# Interface_Pinboard.net
KiCad netlist of a schematic drawn in Altium Designer
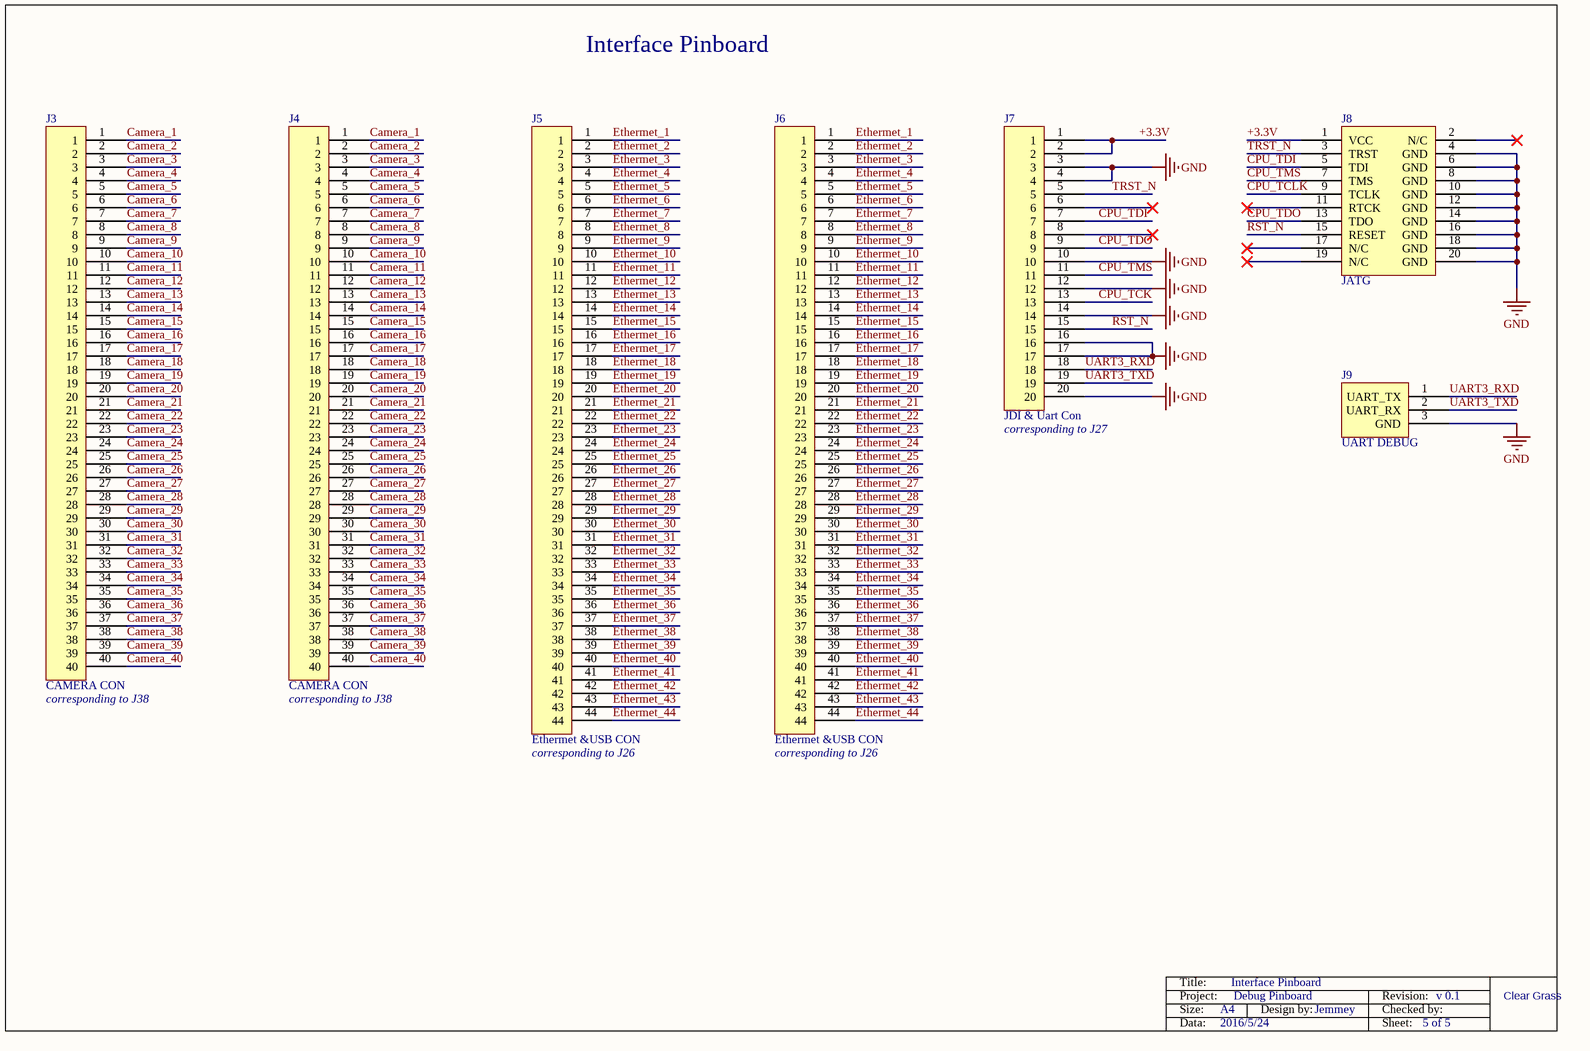
[diagram p0: Interface Pinboard.SchDoc]

(export (version "E")
  (design (tool "Eeschema 10.0.6"))
  (components
    (comp (ref "J3") (value "CAMERA CON") (libsource (lib "Debug Pinborad") (part "CAMERA CON")))
    (comp (ref "J4") (value "CAMERA CON") (libsource (lib "Debug Pinborad") (part "CAMERA CON")))
    (comp (ref "J5")
      (value "Ethermet &USB CON")
      (libsource (lib "Debug Pinborad") (part "Ethermet &USB CON"))
    )
    (comp (ref "J6")
      (value "Ethermet &USB CON")
      (libsource (lib "Debug Pinborad") (part "Ethermet &USB CON"))
    )
    (comp (ref "J7") (value "JDI & Uart Con") (libsource (lib "Debug Pinborad") (part "JDI & Uart Con")))
    (comp (ref "J8") (value "JATG") (libsource (lib "Debug Pinborad") (part "JATG")))
    (comp (ref "J9") (value "UART DEBUG") (libsource (lib "Debug Pinborad") (part "CON")))
  )
  (nets
    (net (code "1") (name "/+3.3V") (class "Default")
      (node (ref "J7") (pin "1") (pinfunction "1_1") (pintype "passive"))
      (node (ref "J7") (pin "2") (pinfunction "2_2") (pintype "passive"))
      (node (ref "J8") (pin "1") (pinfunction "VCC_1") (pintype "passive"))
    )
    (net (code "2") (name "/CPU_TCK") (class "Default")
      (node (ref "J7") (pin "13") (pinfunction "13_13") (pintype "passive"))
    )
    (net (code "3") (name "/CPU_TCLK") (class "Default")
      (node (ref "J8") (pin "9") (pinfunction "TCLK_9") (pintype "passive"))
    )
    (net (code "4") (name "/CPU_TDI") (class "Default")
      (node (ref "J7") (pin "7") (pinfunction "7_7") (pintype "passive"))
      (node (ref "J8") (pin "5") (pinfunction "TDI_5") (pintype "passive"))
    )
    (net (code "5") (name "/CPU_TDO") (class "Default")
      (node (ref "J7") (pin "9") (pinfunction "9_9") (pintype "passive"))
      (node (ref "J8") (pin "13") (pinfunction "TDO_13") (pintype "passive"))
    )
    (net (code "6") (name "/CPU_TMS") (class "Default")
      (node (ref "J7") (pin "11") (pinfunction "11_11") (pintype "passive"))
      (node (ref "J8") (pin "7") (pinfunction "TMS_7") (pintype "passive"))
    )
    (net (code "7") (name "/Camera_1") (class "Default")
      (node (ref "J3") (pin "1") (pinfunction "1_1") (pintype "passive"))
      (node (ref "J4") (pin "1") (pinfunction "1_1") (pintype "passive"))
    )
    (net (code "8") (name "/Camera_2") (class "Default")
      (node (ref "J3") (pin "2") (pinfunction "2_2") (pintype "passive"))
      (node (ref "J4") (pin "2") (pinfunction "2_2") (pintype "passive"))
    )
    (net (code "9") (name "/Camera_3") (class "Default")
      (node (ref "J3") (pin "3") (pinfunction "3_3") (pintype "passive"))
      (node (ref "J4") (pin "3") (pinfunction "3_3") (pintype "passive"))
    )
    (net (code "10") (name "/Camera_4") (class "Default")
      (node (ref "J3") (pin "4") (pinfunction "4_4") (pintype "passive"))
      (node (ref "J4") (pin "4") (pinfunction "4_4") (pintype "passive"))
    )
    (net (code "11") (name "/Camera_5") (class "Default")
      (node (ref "J3") (pin "5") (pinfunction "5_5") (pintype "passive"))
      (node (ref "J4") (pin "5") (pinfunction "5_5") (pintype "passive"))
    )
    (net (code "12") (name "/Camera_6") (class "Default")
      (node (ref "J3") (pin "6") (pinfunction "6_6") (pintype "passive"))
      (node (ref "J4") (pin "6") (pinfunction "6_6") (pintype "passive"))
    )
    (net (code "13") (name "/Camera_7") (class "Default")
      (node (ref "J3") (pin "7") (pinfunction "7_7") (pintype "passive"))
      (node (ref "J4") (pin "7") (pinfunction "7_7") (pintype "passive"))
    )
    (net (code "14") (name "/Camera_8") (class "Default")
      (node (ref "J3") (pin "8") (pinfunction "8_8") (pintype "passive"))
      (node (ref "J4") (pin "8") (pinfunction "8_8") (pintype "passive"))
    )
    (net (code "15") (name "/Camera_9") (class "Default")
      (node (ref "J3") (pin "9") (pinfunction "9_9") (pintype "passive"))
      (node (ref "J4") (pin "9") (pinfunction "9_9") (pintype "passive"))
    )
    (net (code "16") (name "/Camera_10") (class "Default")
      (node (ref "J3") (pin "10") (pinfunction "10_10") (pintype "passive"))
      (node (ref "J4") (pin "10") (pinfunction "10_10") (pintype "passive"))
    )
    (net (code "17") (name "/Camera_11") (class "Default")
      (node (ref "J3") (pin "11") (pinfunction "11_11") (pintype "passive"))
      (node (ref "J4") (pin "11") (pinfunction "11_11") (pintype "passive"))
    )
    (net (code "18") (name "/Camera_12") (class "Default")
      (node (ref "J3") (pin "12") (pinfunction "12_12") (pintype "passive"))
      (node (ref "J4") (pin "12") (pinfunction "12_12") (pintype "passive"))
    )
    (net (code "19") (name "/Camera_13") (class "Default")
      (node (ref "J3") (pin "13") (pinfunction "13_13") (pintype "passive"))
      (node (ref "J4") (pin "13") (pinfunction "13_13") (pintype "passive"))
    )
    (net (code "20") (name "/Camera_14") (class "Default")
      (node (ref "J3") (pin "14") (pinfunction "14_14") (pintype "passive"))
      (node (ref "J4") (pin "14") (pinfunction "14_14") (pintype "passive"))
    )
    (net (code "21") (name "/Camera_15") (class "Default")
      (node (ref "J3") (pin "15") (pinfunction "15_15") (pintype "passive"))
      (node (ref "J4") (pin "15") (pinfunction "15_15") (pintype "passive"))
    )
    (net (code "22") (name "/Camera_16") (class "Default")
      (node (ref "J3") (pin "16") (pinfunction "16_16") (pintype "passive"))
      (node (ref "J4") (pin "16") (pinfunction "16_16") (pintype "passive"))
    )
    (net (code "23") (name "/Camera_17") (class "Default")
      (node (ref "J3") (pin "17") (pinfunction "17_17") (pintype "passive"))
      (node (ref "J4") (pin "17") (pinfunction "17_17") (pintype "passive"))
    )
    (net (code "24") (name "/Camera_18") (class "Default")
      (node (ref "J3") (pin "18") (pinfunction "18_18") (pintype "passive"))
      (node (ref "J4") (pin "18") (pinfunction "18_18") (pintype "passive"))
    )
    (net (code "25") (name "/Camera_19") (class "Default")
      (node (ref "J3") (pin "19") (pinfunction "19_19") (pintype "passive"))
      (node (ref "J4") (pin "19") (pinfunction "19_19") (pintype "passive"))
    )
    (net (code "26") (name "/Camera_20") (class "Default")
      (node (ref "J3") (pin "20") (pinfunction "20_20") (pintype "passive"))
      (node (ref "J4") (pin "20") (pinfunction "20_20") (pintype "passive"))
    )
    (net (code "27") (name "/Camera_21") (class "Default")
      (node (ref "J3") (pin "21") (pinfunction "21_21") (pintype "passive"))
      (node (ref "J4") (pin "21") (pinfunction "21_21") (pintype "passive"))
    )
    (net (code "28") (name "/Camera_22") (class "Default")
      (node (ref "J3") (pin "22") (pinfunction "22_22") (pintype "passive"))
      (node (ref "J4") (pin "22") (pinfunction "22_22") (pintype "passive"))
    )
    (net (code "29") (name "/Camera_23") (class "Default")
      (node (ref "J3") (pin "23") (pinfunction "23_23") (pintype "passive"))
      (node (ref "J4") (pin "23") (pinfunction "23_23") (pintype "passive"))
    )
    (net (code "30") (name "/Camera_24") (class "Default")
      (node (ref "J3") (pin "24") (pinfunction "24_24") (pintype "passive"))
      (node (ref "J4") (pin "24") (pinfunction "24_24") (pintype "passive"))
    )
    (net (code "31") (name "/Camera_25") (class "Default")
      (node (ref "J3") (pin "25") (pinfunction "25_25") (pintype "passive"))
      (node (ref "J4") (pin "25") (pinfunction "25_25") (pintype "passive"))
    )
    (net (code "32") (name "/Camera_26") (class "Default")
      (node (ref "J3") (pin "26") (pinfunction "26_26") (pintype "passive"))
      (node (ref "J4") (pin "26") (pinfunction "26_26") (pintype "passive"))
    )
    (net (code "33") (name "/Camera_27") (class "Default")
      (node (ref "J3") (pin "27") (pinfunction "27_27") (pintype "passive"))
      (node (ref "J4") (pin "27") (pinfunction "27_27") (pintype "passive"))
    )
    (net (code "34") (name "/Camera_28") (class "Default")
      (node (ref "J3") (pin "28") (pinfunction "28_28") (pintype "passive"))
      (node (ref "J4") (pin "28") (pinfunction "28_28") (pintype "passive"))
    )
    (net (code "35") (name "/Camera_29") (class "Default")
      (node (ref "J3") (pin "29") (pinfunction "29_29") (pintype "passive"))
      (node (ref "J4") (pin "29") (pinfunction "29_29") (pintype "passive"))
    )
    (net (code "36") (name "/Camera_30") (class "Default")
      (node (ref "J3") (pin "30") (pinfunction "30_30") (pintype "passive"))
      (node (ref "J4") (pin "30") (pinfunction "30_30") (pintype "passive"))
    )
    (net (code "37") (name "/Camera_31") (class "Default")
      (node (ref "J3") (pin "31") (pinfunction "31_31") (pintype "passive"))
      (node (ref "J4") (pin "31") (pinfunction "31_31") (pintype "passive"))
    )
    (net (code "38") (name "/Camera_32") (class "Default")
      (node (ref "J3") (pin "32") (pinfunction "32_32") (pintype "passive"))
      (node (ref "J4") (pin "32") (pinfunction "32_32") (pintype "passive"))
    )
    (net (code "39") (name "/Camera_33") (class "Default")
      (node (ref "J3") (pin "33") (pinfunction "33_33") (pintype "passive"))
      (node (ref "J4") (pin "33") (pinfunction "33_33") (pintype "passive"))
    )
    (net (code "40") (name "/Camera_34") (class "Default")
      (node (ref "J3") (pin "34") (pinfunction "34_34") (pintype "passive"))
      (node (ref "J4") (pin "34") (pinfunction "34_34") (pintype "passive"))
    )
    (net (code "41") (name "/Camera_35") (class "Default")
      (node (ref "J3") (pin "35") (pinfunction "35_35") (pintype "passive"))
      (node (ref "J4") (pin "35") (pinfunction "35_35") (pintype "passive"))
    )
    (net (code "42") (name "/Camera_36") (class "Default")
      (node (ref "J3") (pin "36") (pinfunction "36_36") (pintype "passive"))
      (node (ref "J4") (pin "36") (pinfunction "36_36") (pintype "passive"))
    )
    (net (code "43") (name "/Camera_37") (class "Default")
      (node (ref "J3") (pin "37") (pinfunction "37_37") (pintype "passive"))
      (node (ref "J4") (pin "37") (pinfunction "37_37") (pintype "passive"))
    )
    (net (code "44") (name "/Camera_38") (class "Default")
      (node (ref "J3") (pin "38") (pinfunction "38_38") (pintype "passive"))
      (node (ref "J4") (pin "38") (pinfunction "38_38") (pintype "passive"))
    )
    (net (code "45") (name "/Camera_39") (class "Default")
      (node (ref "J3") (pin "39") (pinfunction "39_39") (pintype "passive"))
      (node (ref "J4") (pin "39") (pinfunction "39_39") (pintype "passive"))
    )
    (net (code "46") (name "/Camera_40") (class "Default")
      (node (ref "J3") (pin "40") (pinfunction "40_40") (pintype "passive"))
      (node (ref "J4") (pin "40") (pinfunction "40_40") (pintype "passive"))
    )
    (net (code "47") (name "/Ethermet_1") (class "Default")
      (node (ref "J5") (pin "1") (pinfunction "1_1") (pintype "passive"))
      (node (ref "J6") (pin "1") (pinfunction "1_1") (pintype "passive"))
    )
    (net (code "48") (name "/Ethermet_2") (class "Default")
      (node (ref "J5") (pin "2") (pinfunction "2_2") (pintype "passive"))
      (node (ref "J6") (pin "2") (pinfunction "2_2") (pintype "passive"))
    )
    (net (code "49") (name "/Ethermet_2~{2}") (class "Default")
      (node (ref "J5") (pin "22") (pinfunction "22_22") (pintype "passive"))
      (node (ref "J6") (pin "22") (pinfunction "22_22") (pintype "passive"))
    )
    (net (code "50") (name "/Ethermet_3") (class "Default")
      (node (ref "J5") (pin "3") (pinfunction "3_3") (pintype "passive"))
      (node (ref "J6") (pin "3") (pinfunction "3_3") (pintype "passive"))
    )
    (net (code "51") (name "/Ethermet_4") (class "Default")
      (node (ref "J5") (pin "4") (pinfunction "4_4") (pintype "passive"))
      (node (ref "J6") (pin "4") (pinfunction "4_4") (pintype "passive"))
    )
    (net (code "52") (name "/Ethermet_5") (class "Default")
      (node (ref "J5") (pin "5") (pinfunction "5_5") (pintype "passive"))
      (node (ref "J6") (pin "5") (pinfunction "5_5") (pintype "passive"))
    )
    (net (code "53") (name "/Ethermet_6") (class "Default")
      (node (ref "J5") (pin "6") (pinfunction "6_6") (pintype "passive"))
      (node (ref "J6") (pin "6") (pinfunction "6_6") (pintype "passive"))
    )
    (net (code "54") (name "/Ethermet_7") (class "Default")
      (node (ref "J5") (pin "7") (pinfunction "7_7") (pintype "passive"))
      (node (ref "J6") (pin "7") (pinfunction "7_7") (pintype "passive"))
    )
    (net (code "55") (name "/Ethermet_8") (class "Default")
      (node (ref "J5") (pin "8") (pinfunction "8_8") (pintype "passive"))
      (node (ref "J6") (pin "8") (pinfunction "8_8") (pintype "passive"))
    )
    (net (code "56") (name "/Ethermet_9") (class "Default")
      (node (ref "J5") (pin "9") (pinfunction "9_9") (pintype "passive"))
      (node (ref "J6") (pin "9") (pinfunction "9_9") (pintype "passive"))
    )
    (net (code "57") (name "/Ethermet_10") (class "Default")
      (node (ref "J5") (pin "10") (pinfunction "10_10") (pintype "passive"))
      (node (ref "J6") (pin "10") (pinfunction "10_10") (pintype "passive"))
    )
    (net (code "58") (name "/Ethermet_11") (class "Default")
      (node (ref "J5") (pin "11") (pinfunction "11_11") (pintype "passive"))
      (node (ref "J6") (pin "11") (pinfunction "11_11") (pintype "passive"))
    )
    (net (code "59") (name "/Ethermet_12") (class "Default")
      (node (ref "J5") (pin "12") (pinfunction "12_12") (pintype "passive"))
      (node (ref "J6") (pin "12") (pinfunction "12_12") (pintype "passive"))
    )
    (net (code "60") (name "/Ethermet_13") (class "Default")
      (node (ref "J5") (pin "13") (pinfunction "13_13") (pintype "passive"))
      (node (ref "J6") (pin "13") (pinfunction "13_13") (pintype "passive"))
    )
    (net (code "61") (name "/Ethermet_14") (class "Default")
      (node (ref "J5") (pin "14") (pinfunction "14_14") (pintype "passive"))
      (node (ref "J6") (pin "14") (pinfunction "14_14") (pintype "passive"))
    )
    (net (code "62") (name "/Ethermet_15") (class "Default")
      (node (ref "J5") (pin "15") (pinfunction "15_15") (pintype "passive"))
      (node (ref "J6") (pin "15") (pinfunction "15_15") (pintype "passive"))
    )
    (net (code "63") (name "/Ethermet_16") (class "Default")
      (node (ref "J5") (pin "16") (pinfunction "16_16") (pintype "passive"))
      (node (ref "J6") (pin "16") (pinfunction "16_16") (pintype "passive"))
    )
    (net (code "64") (name "/Ethermet_17") (class "Default")
      (node (ref "J5") (pin "17") (pinfunction "17_17") (pintype "passive"))
      (node (ref "J6") (pin "17") (pinfunction "17_17") (pintype "passive"))
    )
    (net (code "65") (name "/Ethermet_18") (class "Default")
      (node (ref "J5") (pin "18") (pinfunction "18_18") (pintype "passive"))
      (node (ref "J6") (pin "18") (pinfunction "18_18") (pintype "passive"))
    )
    (net (code "66") (name "/Ethermet_19") (class "Default")
      (node (ref "J5") (pin "19") (pinfunction "19_19") (pintype "passive"))
      (node (ref "J6") (pin "19") (pinfunction "19_19") (pintype "passive"))
    )
    (net (code "67") (name "/Ethermet_20") (class "Default")
      (node (ref "J5") (pin "20") (pinfunction "20_20") (pintype "passive"))
      (node (ref "J6") (pin "20") (pinfunction "20_20") (pintype "passive"))
    )
    (net (code "68") (name "/Ethermet_21") (class "Default")
      (node (ref "J5") (pin "21") (pinfunction "21_21") (pintype "passive"))
      (node (ref "J6") (pin "21") (pinfunction "21_21") (pintype "passive"))
    )
    (net (code "69") (name "/Ethermet_23") (class "Default")
      (node (ref "J5") (pin "23") (pinfunction "23_23") (pintype "passive"))
      (node (ref "J6") (pin "23") (pinfunction "23_23") (pintype "passive"))
    )
    (net (code "70") (name "/Ethermet_24") (class "Default")
      (node (ref "J5") (pin "24") (pinfunction "24_24") (pintype "passive"))
      (node (ref "J6") (pin "24") (pinfunction "24_24") (pintype "passive"))
    )
    (net (code "71") (name "/Ethermet_25") (class "Default")
      (node (ref "J5") (pin "25") (pinfunction "25_25") (pintype "passive"))
      (node (ref "J6") (pin "25") (pinfunction "25_25") (pintype "passive"))
    )
    (net (code "72") (name "/Ethermet_26") (class "Default")
      (node (ref "J5") (pin "26") (pinfunction "26_26") (pintype "passive"))
      (node (ref "J6") (pin "26") (pinfunction "26_26") (pintype "passive"))
    )
    (net (code "73") (name "/Ethermet_27") (class "Default")
      (node (ref "J5") (pin "27") (pinfunction "27_27") (pintype "passive"))
      (node (ref "J6") (pin "27") (pinfunction "27_27") (pintype "passive"))
    )
    (net (code "74") (name "/Ethermet_28") (class "Default")
      (node (ref "J5") (pin "28") (pinfunction "28_28") (pintype "passive"))
      (node (ref "J6") (pin "28") (pinfunction "28_28") (pintype "passive"))
    )
    (net (code "75") (name "/Ethermet_29") (class "Default")
      (node (ref "J5") (pin "29") (pinfunction "29_29") (pintype "passive"))
      (node (ref "J6") (pin "29") (pinfunction "29_29") (pintype "passive"))
    )
    (net (code "76") (name "/Ethermet_30") (class "Default")
      (node (ref "J5") (pin "30") (pinfunction "30_30") (pintype "passive"))
      (node (ref "J6") (pin "30") (pinfunction "30_30") (pintype "passive"))
    )
    (net (code "77") (name "/Ethermet_31") (class "Default")
      (node (ref "J5") (pin "31") (pinfunction "31_31") (pintype "passive"))
      (node (ref "J6") (pin "31") (pinfunction "31_31") (pintype "passive"))
    )
    (net (code "78") (name "/Ethermet_32") (class "Default")
      (node (ref "J5") (pin "32") (pinfunction "32_32") (pintype "passive"))
      (node (ref "J6") (pin "32") (pinfunction "32_32") (pintype "passive"))
    )
    (net (code "79") (name "/Ethermet_33") (class "Default")
      (node (ref "J5") (pin "33") (pinfunction "33_33") (pintype "passive"))
      (node (ref "J6") (pin "33") (pinfunction "33_33") (pintype "passive"))
    )
    (net (code "80") (name "/Ethermet_34") (class "Default")
      (node (ref "J5") (pin "34") (pinfunction "34_34") (pintype "passive"))
      (node (ref "J6") (pin "34") (pinfunction "34_34") (pintype "passive"))
    )
    (net (code "81") (name "/Ethermet_35") (class "Default")
      (node (ref "J5") (pin "35") (pinfunction "35_35") (pintype "passive"))
      (node (ref "J6") (pin "35") (pinfunction "35_35") (pintype "passive"))
    )
    (net (code "82") (name "/Ethermet_36") (class "Default")
      (node (ref "J5") (pin "36") (pinfunction "36_36") (pintype "passive"))
      (node (ref "J6") (pin "36") (pinfunction "36_36") (pintype "passive"))
    )
    (net (code "83") (name "/Ethermet_37") (class "Default")
      (node (ref "J5") (pin "37") (pinfunction "37_37") (pintype "passive"))
      (node (ref "J6") (pin "37") (pinfunction "37_37") (pintype "passive"))
    )
    (net (code "84") (name "/Ethermet_38") (class "Default")
      (node (ref "J5") (pin "38") (pinfunction "38_38") (pintype "passive"))
      (node (ref "J6") (pin "38") (pinfunction "38_38") (pintype "passive"))
    )
    (net (code "85") (name "/Ethermet_39") (class "Default")
      (node (ref "J5") (pin "39") (pinfunction "39_39") (pintype "passive"))
      (node (ref "J6") (pin "39") (pinfunction "39_39") (pintype "passive"))
    )
    (net (code "86") (name "/Ethermet_40") (class "Default")
      (node (ref "J5") (pin "40") (pinfunction "40_40") (pintype "passive"))
      (node (ref "J6") (pin "40") (pinfunction "40_40") (pintype "passive"))
    )
    (net (code "87") (name "/Ethermet_41") (class "Default")
      (node (ref "J5") (pin "41") (pinfunction "41_41") (pintype "passive"))
      (node (ref "J6") (pin "41") (pinfunction "41_41") (pintype "passive"))
    )
    (net (code "88") (name "/Ethermet_42") (class "Default")
      (node (ref "J5") (pin "42") (pinfunction "42_42") (pintype "passive"))
      (node (ref "J6") (pin "42") (pinfunction "42_42") (pintype "passive"))
    )
    (net (code "89") (name "/Ethermet_43") (class "Default")
      (node (ref "J5") (pin "43") (pinfunction "43_43") (pintype "passive"))
      (node (ref "J6") (pin "43") (pinfunction "43_43") (pintype "passive"))
    )
    (net (code "90") (name "/Ethermet_44") (class "Default")
      (node (ref "J5") (pin "44") (pinfunction "44_44") (pintype "passive"))
      (node (ref "J6") (pin "44") (pinfunction "44_44") (pintype "passive"))
    )
    (net (code "91") (name "/RST_N") (class "Default")
      (node (ref "J7") (pin "15") (pinfunction "15_15") (pintype "passive"))
      (node (ref "J8") (pin "15") (pinfunction "RESET_15") (pintype "passive"))
    )
    (net (code "92") (name "/TRST_N") (class "Default")
      (node (ref "J7") (pin "5") (pinfunction "5_5") (pintype "passive"))
      (node (ref "J8") (pin "3") (pinfunction "TRST_3") (pintype "passive"))
    )
    (net (code "93") (name "/UART3_RXD") (class "Default")
      (node (ref "J7") (pin "18") (pinfunction "18_18") (pintype "passive"))
      (node (ref "J9") (pin "1") (pinfunction "UART_TX_1") (pintype "passive"))
    )
    (net (code "94") (name "/UART3_TXD") (class "Default")
      (node (ref "J7") (pin "19") (pinfunction "19_19") (pintype "passive"))
      (node (ref "J9") (pin "2") (pinfunction "UART_RX_2") (pintype "passive"))
    )
    (net (code "95") (name "GND") (class "Default")
      (node (ref "J7") (pin "10") (pinfunction "10_10") (pintype "passive"))
      (node (ref "J7") (pin "12") (pinfunction "12_12") (pintype "passive"))
      (node (ref "J7") (pin "14") (pinfunction "14_14") (pintype "passive"))
      (node (ref "J7") (pin "16") (pinfunction "16_16") (pintype "passive"))
      (node (ref "J7") (pin "17") (pinfunction "17_17") (pintype "passive"))
      (node (ref "J7") (pin "20") (pinfunction "20_20") (pintype "passive"))
      (node (ref "J7") (pin "3") (pinfunction "3_3") (pintype "passive"))
      (node (ref "J7") (pin "4") (pinfunction "4_4") (pintype "passive"))
      (node (ref "J8") (pin "10") (pinfunction "GND_10") (pintype "passive"))
      (node (ref "J8") (pin "12") (pinfunction "GND_12") (pintype "passive"))
      (node (ref "J8") (pin "14") (pinfunction "GND_14") (pintype "passive"))
      (node (ref "J8") (pin "16") (pinfunction "GND_16") (pintype "passive"))
      (node (ref "J8") (pin "18") (pinfunction "GND_18") (pintype "passive"))
      (node (ref "J8") (pin "20") (pinfunction "GND_20") (pintype "passive"))
      (node (ref "J8") (pin "4") (pinfunction "GND_4") (pintype "passive"))
      (node (ref "J8") (pin "6") (pinfunction "GND_6") (pintype "passive"))
      (node (ref "J8") (pin "8") (pinfunction "GND_8") (pintype "passive"))
      (node (ref "J9") (pin "3") (pinfunction "GND_3") (pintype "passive"))
    )
    (net (code "96") (name "unconnected-(J7-Pad6)") (class "Default")
      (node (ref "J7") (pin "6") (pinfunction "6_6") (pintype "passive+no_connect"))
    )
    (net (code "97") (name "unconnected-(J7-Pad8)") (class "Default")
      (node (ref "J7") (pin "8") (pinfunction "8_8") (pintype "passive+no_connect"))
    )
    (net (code "98") (name "unconnected-(J8-N{slash}C-Pad2)") (class "Default")
      (node (ref "J8") (pin "2") (pinfunction "N/C_2") (pintype "passive+no_connect"))
    )
    (net (code "99") (name "unconnected-(J8-N{slash}C-Pad17)") (class "Default")
      (node (ref "J8") (pin "17") (pinfunction "N/C_17") (pintype "passive+no_connect"))
    )
    (net (code "100") (name "unconnected-(J8-N{slash}C-Pad19)") (class "Default")
      (node (ref "J8") (pin "19") (pinfunction "N/C_19") (pintype "passive+no_connect"))
    )
    (net (code "101") (name "unconnected-(J8-RTCK-Pad11)") (class "Default")
      (node (ref "J8") (pin "11") (pinfunction "RTCK_11") (pintype "passive+no_connect"))
    )
  )
)
